# 01_main.net
KiCad netlist of a schematic drawn in Altium Designer
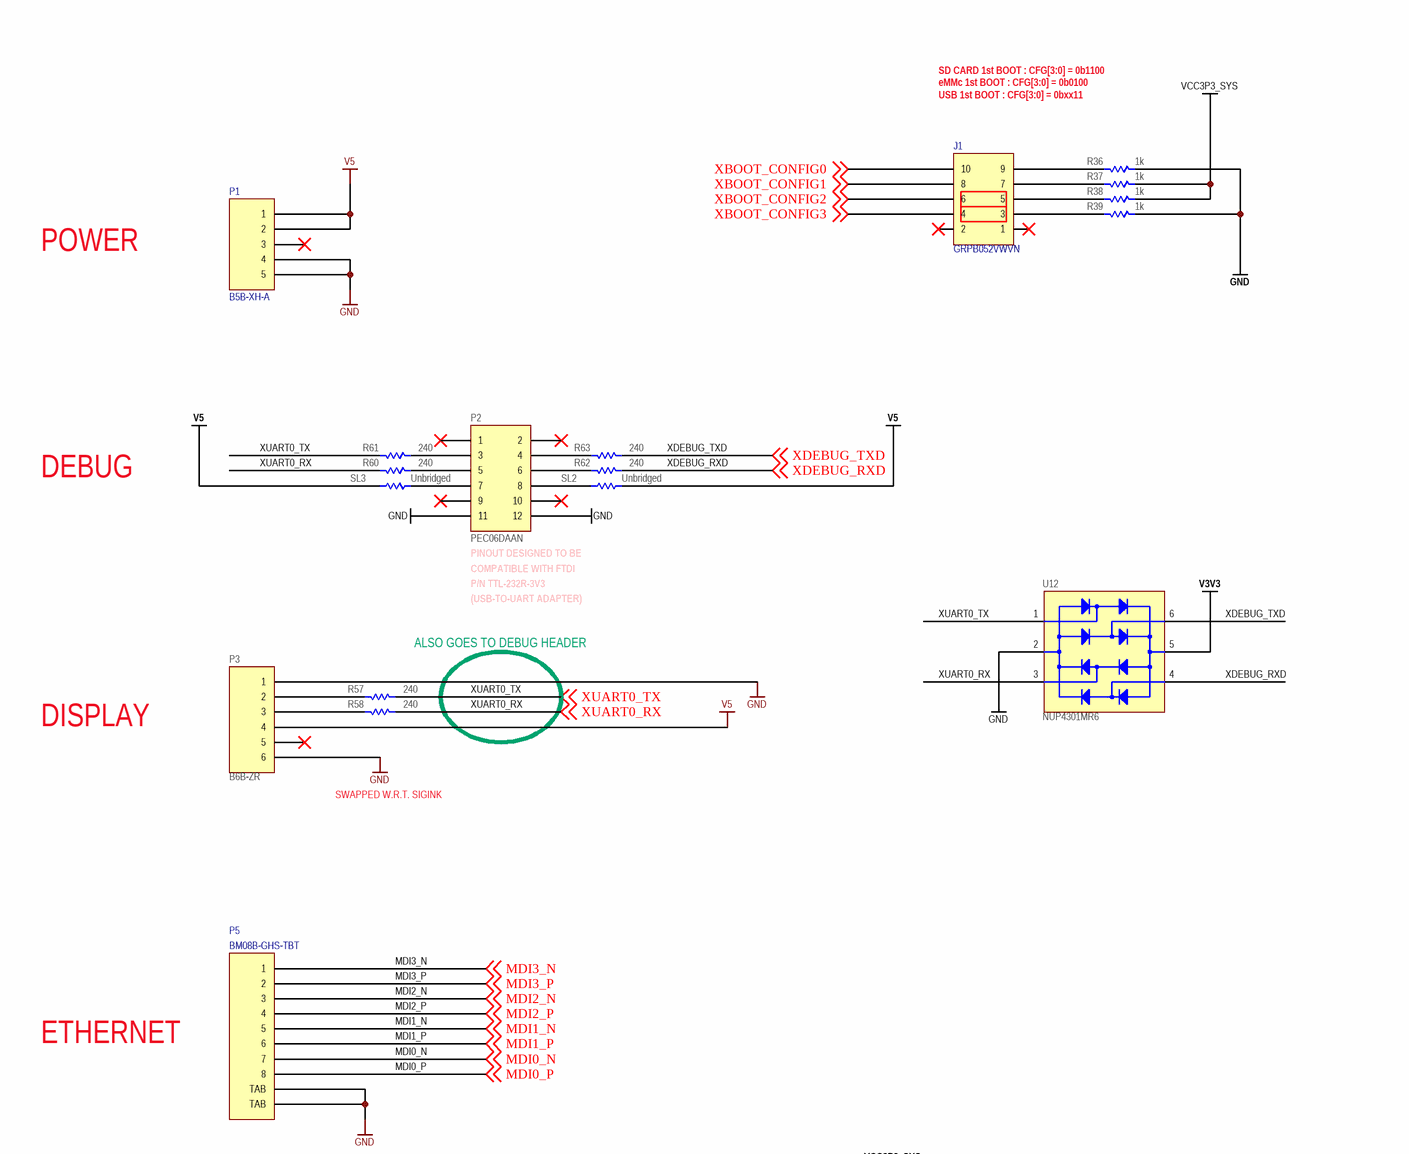
[diagram p0: 01_main.SchDoc, top left]
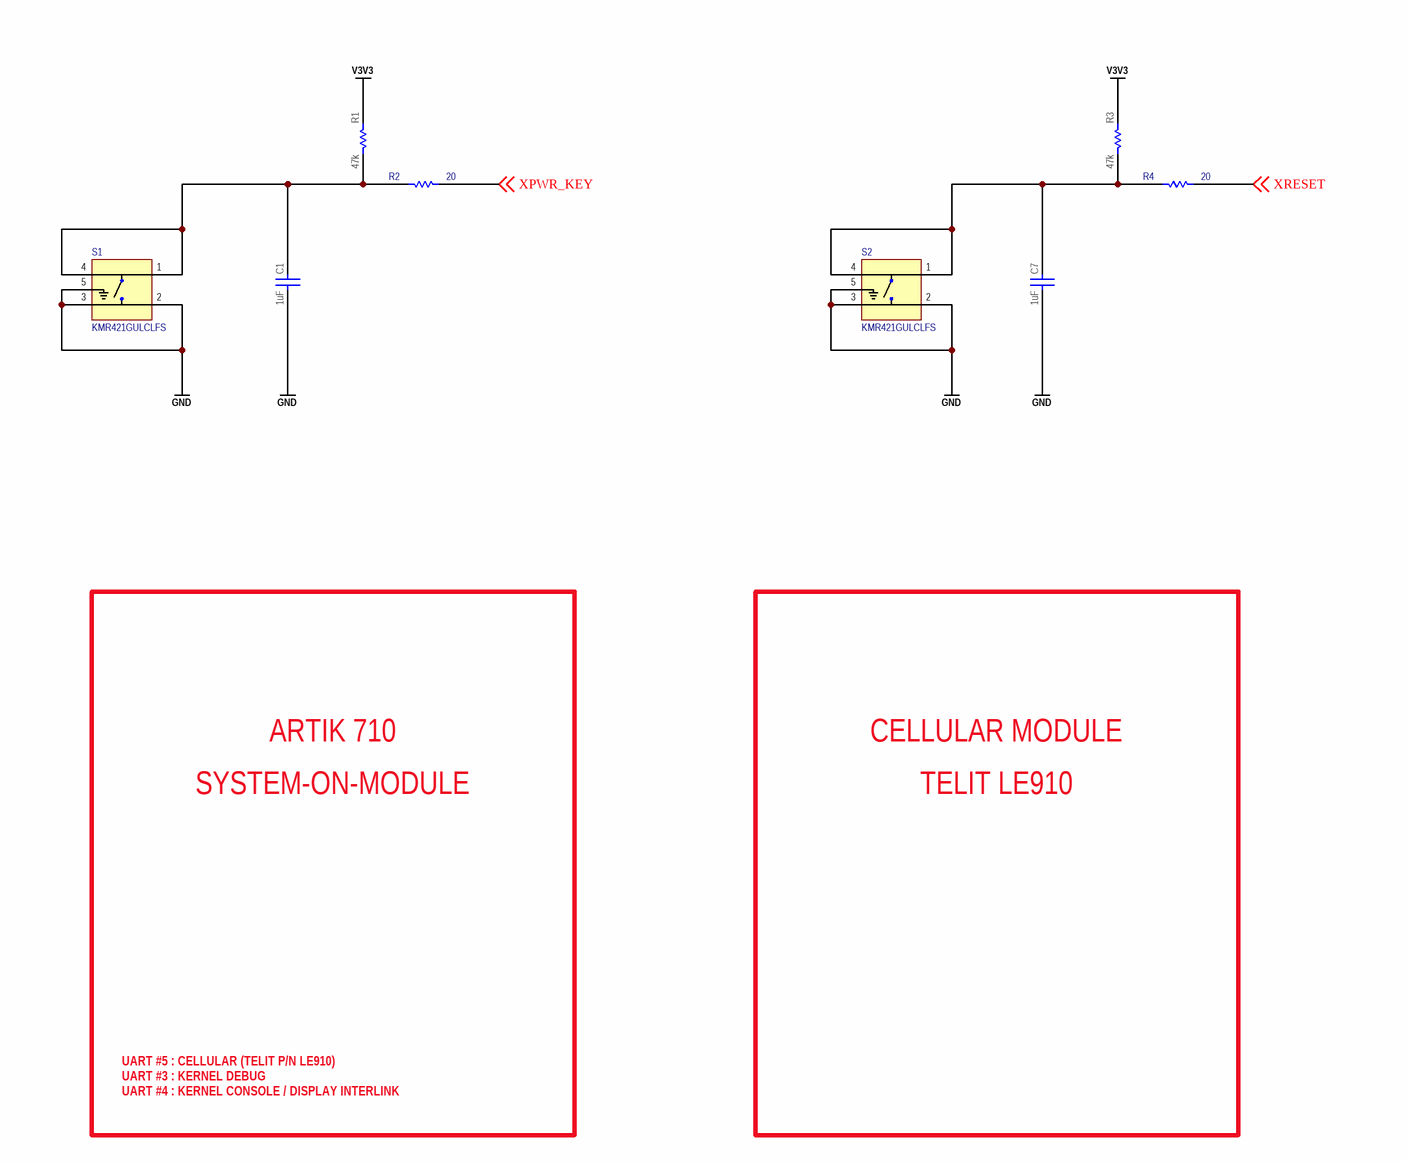
[diagram p1: 01_main.SchDoc, top right]
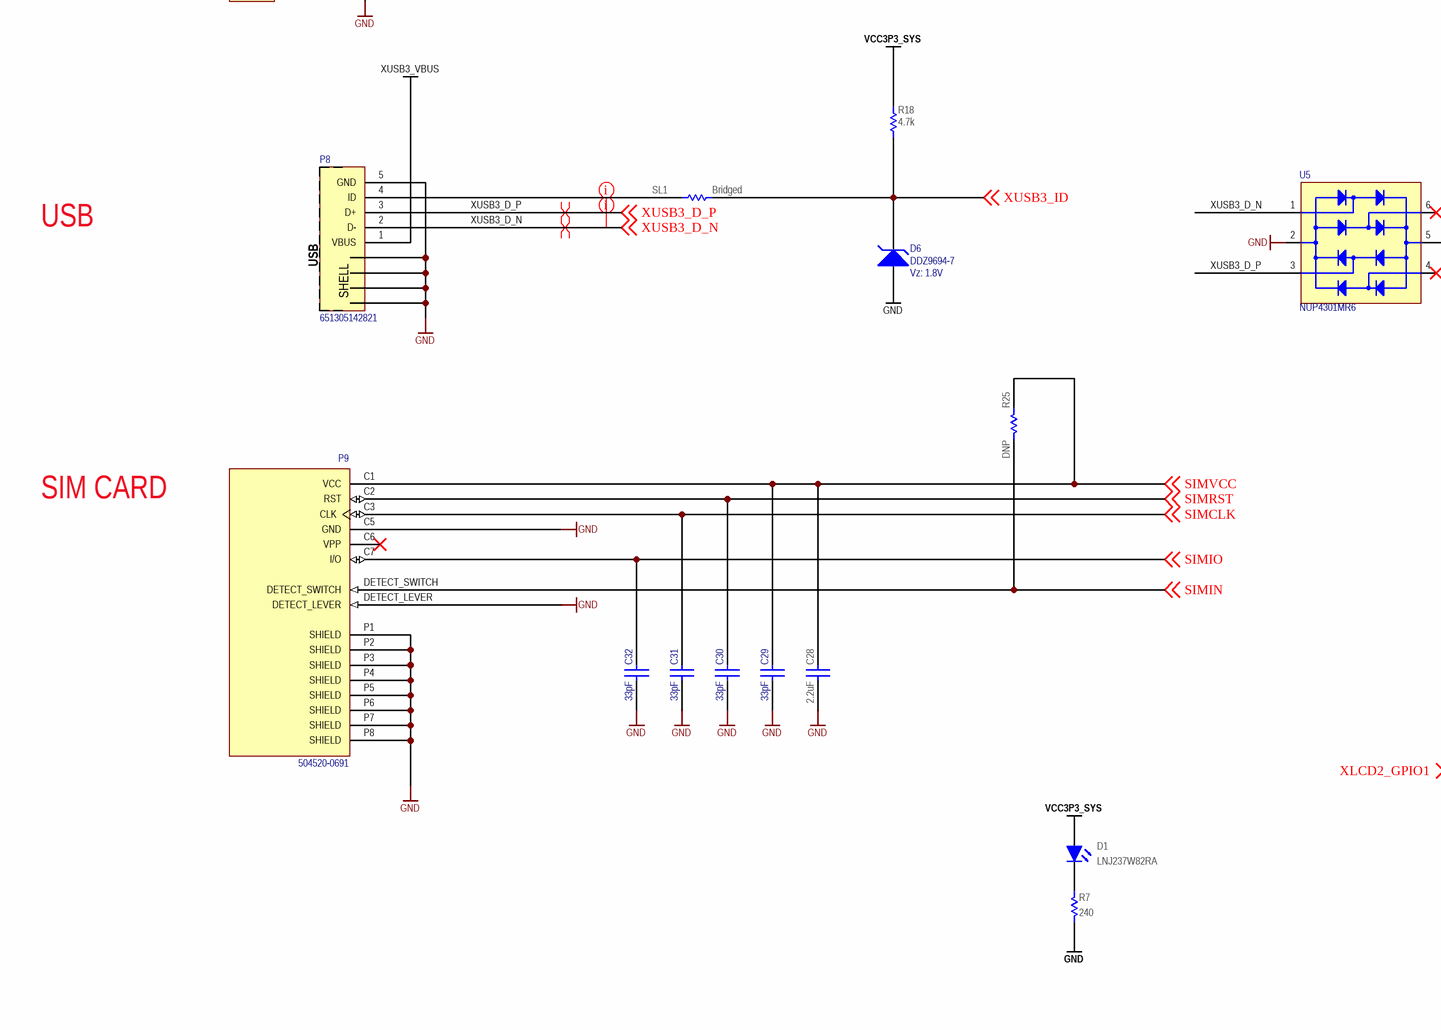
[diagram p2: 01_main.SchDoc, bottom left]
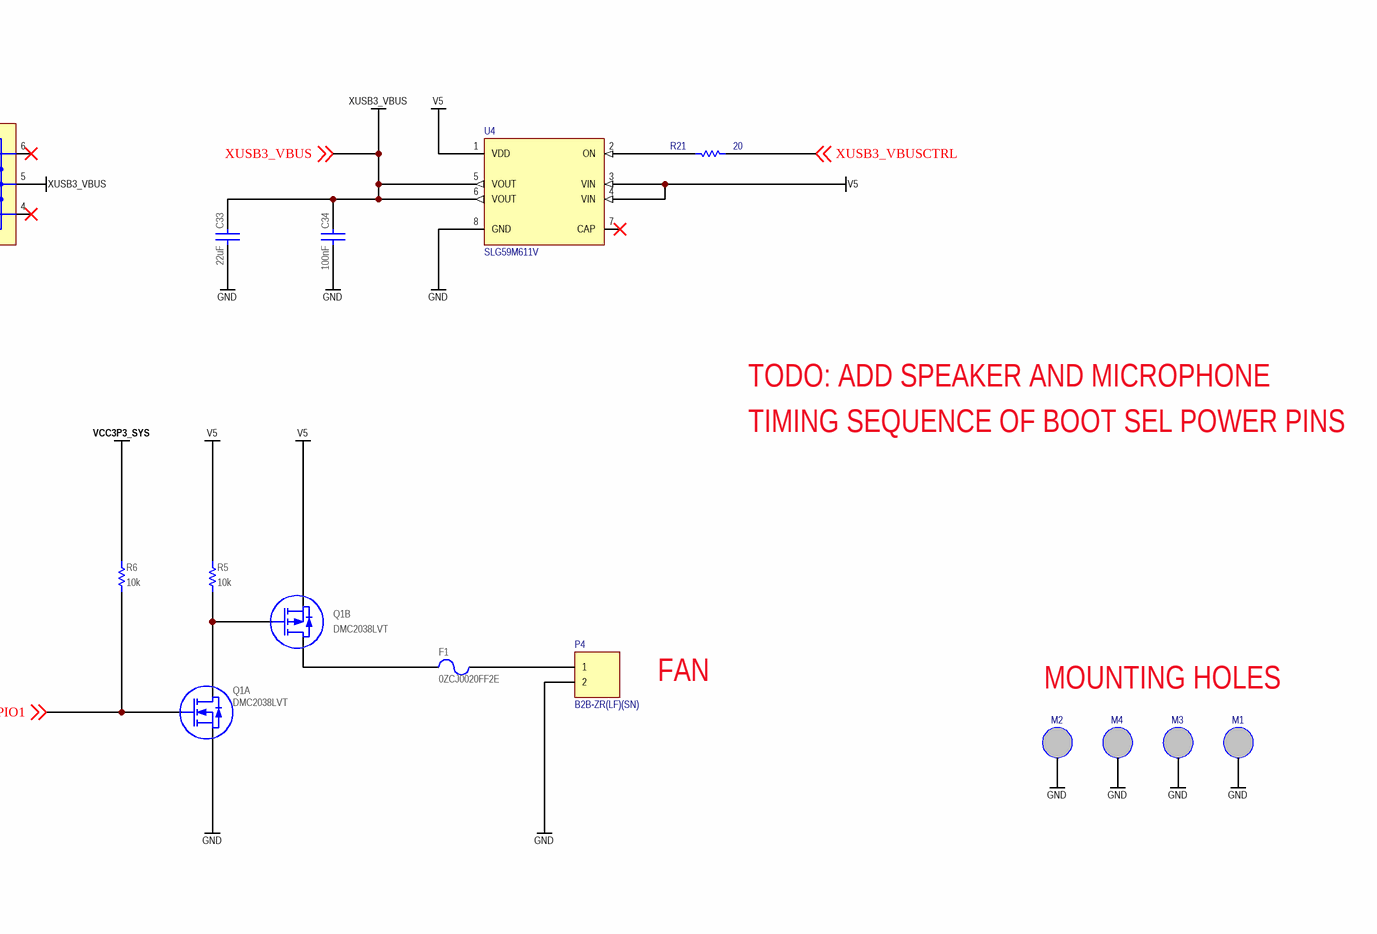
[diagram p3: 01_main.SchDoc, bottom right]

(export (version "E")
  (design (tool "Eeschema 10.0.6"))
  (components
    (comp (ref "C1")
      (value "1uF")
      (footprint "CAPC160X80X90L20N")
      (description "Ceramic Capacitor 1uF ±20% 10V X7R 0603")
      (fields (field (name "MANUFACTURER") "TDK") (field (name "TOLERANCE") "±20%"))
      (libsource (lib "generic") (part "CAP"))
    )
    (comp (ref "C7")
      (value "1uF")
      (footprint "CAPC160X80X90L20N")
      (description "Ceramic Capacitor 1uF ±20% 10V X7R 0603")
      (fields (field (name "MANUFACTURER") "TDK") (field (name "TOLERANCE") "±20%"))
      (libsource (lib "generic") (part "CAP"))
    )
    (comp (ref "C28")
      (value "2.2uF")
      (footprint "CAPC160X80X90L20N")
      (description "Ceramic Capacitor 2.2uF ±20% 10V X7R 0603")
      (fields (field (name "MANUFACTURER") "TDK") (field (name "TOLERANCE") "±20%"))
      (libsource (lib "generic") (part "CAP"))
    )
    (comp (ref "C29")
      (value "33pF")
      (footprint "0402")
      (description "Ceramic Capacitor 33pF ±1% 50V NP0 0402")
      (fields (field (name "VOLTAGE") "50V") (field (name "MANUFACTURER") "Kemet"))
      (libsource (lib "Graviton") (part "CAP 0603"))
    )
    (comp (ref "C30")
      (value "33pF")
      (footprint "0402")
      (description "Ceramic Capacitor 33pF ±1% 50V NP0 0402")
      (fields (field (name "VOLTAGE") "50V") (field (name "MANUFACTURER") "Kemet"))
      (libsource (lib "Graviton") (part "CAP 0603"))
    )
    (comp (ref "C31")
      (value "33pF")
      (footprint "0402")
      (description "Ceramic Capacitor 33pF ±1% 50V NP0 0402")
      (fields (field (name "VOLTAGE") "50V") (field (name "MANUFACTURER") "Kemet"))
      (libsource (lib "Graviton") (part "CAP 0603"))
    )
    (comp (ref "C32")
      (value "33pF")
      (footprint "0402")
      (description "Ceramic Capacitor 33pF ±1% 50V NP0 0402")
      (fields (field (name "VOLTAGE") "50V") (field (name "MANUFACTURER") "Kemet"))
      (libsource (lib "Graviton") (part "CAP 0603"))
    )
    (comp (ref "C33")
      (value "22uF")
      (footprint "CAPC200X125X145L45N")
      (description "Ceramic Capacitor 22uF ±20% 10V X7S 0805")
      (fields (field (name "MANUFACTURER") "TDK") (field (name "TOLERANCE") "±20%"))
      (libsource (lib "generic") (part "CAP"))
    )
    (comp (ref "C34")
      (value "100nF")
      (footprint "CAPC100X50X55L25N")
      (description "Ceramic Capacitor 100nF ±10% 50V X7R 0402")
      (fields (field (name "MANUFACTURER") "Murata") (field (name "TOLERANCE") "±10%"))
      (libsource (lib "generic") (part "CAP"))
    )
    (comp (ref "D1")
      (value "LNJ237W82RA")
      (footprint "0603_LED")
      (description "LED, SMT 0603, Color Red, 5mA, 1.85V")
      (fields (field (name "MANUFACTURER") "Panasonic"))
      (libsource (lib "generic") (part "LED0603RD"))
    )
    (comp (ref "D6")
      (value "DDZ9694-7")
      (footprint "generic:SOD123")
      (description "Zener Diode 1.8V 500mW SOD123")
      (fields (field (name "MANUFACTURER") "Diodes, Inc.") (field (name "VZ") "1.8V"))
      (libsource (lib "diodes_inc") (part "DDZ9694-7"))
    )
    (comp (ref "F1")
      (value "0ZCJ0020FF2E")
      (footprint "generic:1206")
      (description "PTC Resettable Fuse, 0.2A, 30V, SMD 1206")
      (fields (field (name "MANUFACTURER") "Bell Fuse"))
      (libsource (lib "bel-fuse") (part "0ZCJ0020FF2E"))
    )
    (comp (ref "J1")
      (value "GRPB052VWVN")
      (footprint "sullins:GRPB052VWVN")
      (description "Male Header, 0.050\" Pitch, 2x5 Position")
      (fields (field (name "MANUFACTURER") "Sullins"))
      (libsource (lib "sullins") (part "GRPB052VWVN"))
    )
    (comp (ref "M1") (value "MOUNT350") (footprint "mount350") (libsource (lib "Misc") (part "M3_HOLE")))
    (comp (ref "M2") (value "MOUNT350") (footprint "mount350") (libsource (lib "Misc") (part "M3_HOLE")))
    (comp (ref "M3") (value "MOUNT350") (footprint "mount350") (libsource (lib "Misc") (part "M3_HOLE")))
    (comp (ref "M4") (value "MOUNT350") (footprint "mount350") (libsource (lib "Misc") (part "M3_HOLE")))
    (comp (ref "P1")
      (value "B5B-XH-A")
      (footprint "jst:B5B-XH-A")
      (description "2.5mm pitch 5-position")
      (fields (field (name "MANUFACTURER") "JST"))
      (libsource (lib "jst") (part "B5B-XH-A"))
    )
    (comp (ref "P2")
      (value "PEC06DAAN")
      (footprint "HDR2X6")
      (description "Header, 6-Pin, Dual row")
      (fields (field (name "MANUFACTURER") "Sullins"))
      (libsource (lib "Miscellaneous Connectors") (part "Header 6X2H"))
    )
    (comp (ref "P3")
      (value "B6B-ZR")
      (footprint "B6B-ZR")
      (description "Header, 6-Pin, Single row, Vertical")
      (fields (field (name "MANUFACTURER") "JST"))
      (libsource (lib "Sigink") (part "TBD"))
    )
    (comp (ref "P4")
      (value "B2B-ZR(LF)(SN)")
      (footprint "B2B-ZR")
      (description "Header, 2-Pin")
      (fields (field (name "MANUFACTURER") "JST"))
      (libsource (lib "Miscellaneous Connectors") (part "Header 2"))
    )
    (comp (ref "P5")
      (value "BM08B-GHS-TBT")
      (footprint "jst:BM08B-GHS-TBT")
      (description "Top Entry Shrouded Connector; 8-position")
      (fields (field (name "MANUFACTURER") "JST"))
      (libsource (lib "jst") (part "BM08B-GHS-TBT"))
    )
    (comp (ref "P8")
      (value "651305142821")
      (footprint "651305142821")
      (description "Right Angle SMT USB Type-AB Connector Receptacle")
      (fields (field (name "MANUFACTURER") "Wurth Elektronik"))
      (libsource (lib "wurth") (part "651305142821"))
    )
    (comp (ref "P9")
      (value "504520-0691")
      (footprint "504520-0691")
      (description "micro-SIM Card Connector")
      (fields (field (name "MANUFACTURER") "Molex"))
      (libsource (lib "molex") (part "504520-0691"))
    )
    (comp (ref "Q1")
      (value "DMC2038LVT")
      (footprint "generic:TSOP-6")
      (description "Complementary MOSFET Pair")
      (fields (field (name "MANUFACTURER") "Diodes, Inc."))
      (libsource (lib "diodes_inc") (part "DMC2038LVT"))
    )
    (comp (ref "R1")
      (value "47k")
      (footprint "RESC1005X40N")
      (description "Thick Film Resistor 47k ±1% 0.1W 75V 0402")
      (fields (field (name "TOLERANCE") "±1%") (field (name "MANUFACTURER") "Panasonic"))
      (libsource (lib "generic") (part "RES"))
    )
    (comp (ref "R2")
      (value "20")
      (footprint "generic:0402")
      (description "Thick Film Resistor 20 ±1% 0402")
      (fields (field (name "MANUFACTURER") "Panasonic") (field (name "TOLERANCE") "±1%"))
      (libsource (lib "altium-import") (part "root_2_mirrored_RES 0402_"))
    )
    (comp (ref "R3")
      (value "47k")
      (footprint "RESC1005X40N")
      (description "Thick Film Resistor 47k ±1% 0.1W 75V 0402")
      (fields (field (name "TOLERANCE") "±1%") (field (name "MANUFACTURER") "Panasonic"))
      (libsource (lib "generic") (part "RES"))
    )
    (comp (ref "R4")
      (value "20")
      (footprint "generic:0402")
      (description "Thick Film Resistor 20 ±1% 0402")
      (fields (field (name "MANUFACTURER") "Panasonic") (field (name "TOLERANCE") "±1%"))
      (libsource (lib "altium-import") (part "root_2_mirrored_RES 0402_"))
    )
    (comp (ref "R5")
      (value "10k")
      (footprint "RESC1005X40N")
      (description "Thick Film Resistor 10k ±1% 0.1W 0402")
      (fields (field (name "MANUFACTURER") "Panasonic") (field (name "TOLERANCE") "±1%"))
      (libsource (lib "generic") (part "RES"))
    )
    (comp (ref "R6")
      (value "10k")
      (footprint "RESC1005X40N")
      (description "Thick Film Resistor 10k ±1% 0.1W 0402")
      (fields (field (name "MANUFACTURER") "Panasonic") (field (name "TOLERANCE") "±1%"))
      (libsource (lib "generic") (part "RES"))
    )
    (comp (ref "R7")
      (value "240")
      (footprint "RESC1005X40N")
      (description "Thick Film Resistor 240 ±1% 0.1W 75V 0402")
      (fields (field (name "TOLERANCE") "±1%") (field (name "MANUFACTURER") "Panasonic"))
      (libsource (lib "generic") (part "RES"))
    )
    (comp (ref "R18")
      (value "4.7k")
      (footprint "RESC1005X40N")
      (description "Thick Film Resistor 4.7k ±1% 0.1W 75V 0402")
      (fields (field (name "TOLERANCE") "±1%") (field (name "MANUFACTURER") "Panasonic"))
      (libsource (lib "generic") (part "RES"))
    )
    (comp (ref "R21")
      (value "20")
      (footprint "generic:0402")
      (description "Thick Film Resistor 20 ±1% 0402")
      (fields (field (name "MANUFACTURER") "Panasonic") (field (name "TOLERANCE") "±1%"))
      (libsource (lib "altium-import") (part "root_2_mirrored_RES 0402_"))
    )
    (comp (ref "R25")
      (value "ERJ-2RKF4702X")
      (footprint "RESC1005X40N")
      (description "Thick Film Resistor 47k ±1% 0.1W 75V 0402")
      (fields
        (field (name "TOLERANCE") "±1%")
        (field (name "MANUFACTURER") "Panasonic")
        (field (name "DO NOT PLACE") "DNP")
      )
      (libsource (lib "generic") (part "RES"))
    )
    (comp (ref "R36")
      (value "1k")
      (footprint "RESC1005X40N")
      (description "Thick Film Resistor 1k ±1% 0.1W 0402")
      (fields (field (name "TOLERANCE") "±1%") (field (name "MANUFACTURER") "Panasonic"))
      (libsource (lib "generic") (part "RES"))
    )
    (comp (ref "R37")
      (value "1k")
      (footprint "RESC1005X40N")
      (description "Thick Film Resistor 1k ±1% 0.1W 0402")
      (fields (field (name "TOLERANCE") "±1%") (field (name "MANUFACTURER") "Panasonic"))
      (libsource (lib "generic") (part "RES"))
    )
    (comp (ref "R38")
      (value "1k")
      (footprint "RESC1005X40N")
      (description "Thick Film Resistor 1k ±1% 0.1W 0402")
      (fields (field (name "TOLERANCE") "±1%") (field (name "MANUFACTURER") "Panasonic"))
      (libsource (lib "generic") (part "RES"))
    )
    (comp (ref "R39")
      (value "1k")
      (footprint "RESC1005X40N")
      (description "Thick Film Resistor 1k ±1% 0.1W 0402")
      (fields (field (name "TOLERANCE") "±1%") (field (name "MANUFACTURER") "Panasonic"))
      (libsource (lib "generic") (part "RES"))
    )
    (comp (ref "R57")
      (value "240")
      (footprint "RESC1005X40N")
      (description "Thick Film Resistor 240 ±1% 0.1W 75V 0402")
      (fields (field (name "TOLERANCE") "±1%") (field (name "MANUFACTURER") "Panasonic"))
      (libsource (lib "generic") (part "RES"))
    )
    (comp (ref "R58")
      (value "240")
      (footprint "RESC1005X40N")
      (description "Thick Film Resistor 240 ±1% 0.1W 75V 0402")
      (fields (field (name "TOLERANCE") "±1%") (field (name "MANUFACTURER") "Panasonic"))
      (libsource (lib "generic") (part "RES"))
    )
    (comp (ref "R60")
      (value "240")
      (footprint "RESC1005X40N")
      (description "Thick Film Resistor 240 ±1% 0.1W 75V 0402")
      (fields (field (name "TOLERANCE") "±1%") (field (name "MANUFACTURER") "Panasonic"))
      (libsource (lib "generic") (part "RES"))
    )
    (comp (ref "R61")
      (value "240")
      (footprint "RESC1005X40N")
      (description "Thick Film Resistor 240 ±1% 0.1W 75V 0402")
      (fields (field (name "TOLERANCE") "±1%") (field (name "MANUFACTURER") "Panasonic"))
      (libsource (lib "generic") (part "RES"))
    )
    (comp (ref "R62")
      (value "240")
      (footprint "RESC1005X40N")
      (description "Thick Film Resistor 240 ±1% 0.1W 75V 0402")
      (fields (field (name "TOLERANCE") "±1%") (field (name "MANUFACTURER") "Panasonic"))
      (libsource (lib "generic") (part "RES"))
    )
    (comp (ref "R63")
      (value "240")
      (footprint "RESC1005X40N")
      (description "Thick Film Resistor 240 ±1% 0.1W 75V 0402")
      (fields (field (name "TOLERANCE") "±1%") (field (name "MANUFACTURER") "Panasonic"))
      (libsource (lib "generic") (part "RES"))
    )
    (comp (ref "S1")
      (value "KMR421GULCLFS")
      (footprint "SW_KMR421GULCLFS")
      (description "Switch Tactile N.O. SPST Round Button Gull Wing 0.05A 32VDC 1VA 200000Cycles 2N SMD Automotive T/R")
      (fields (field (name "MANUFACTURER") "C&K Components"))
      (libsource (lib "c&k") (part "KMR421GULCLFS"))
    )
    (comp (ref "S2")
      (value "KMR421GULCLFS")
      (footprint "SW_KMR421GULCLFS")
      (description "Switch Tactile N.O. SPST Round Button Gull Wing 0.05A 32VDC 1VA 200000Cycles 2N SMD Automotive T/R")
      (fields (field (name "MANUFACTURER") "C&K Components"))
      (libsource (lib "c&k") (part "KMR421GULCLFS"))
    )
    (comp (ref "SL1")
      (value "Bridged")
      (footprint "SOLDERLINK0603X26N_BRIDGED")
      (description "Solder Link Bridged")
      (fields (field (name "Comment") "SOLDER_LINK_BRIDGED"))
      (libsource (lib "generic") (part "RES"))
    )
    (comp (ref "SL2")
      (value "Unbridged")
      (footprint "SOLDERLINK0603X26N")
      (description "Solder Link Unbridged")
      (fields (field (name "Comment") "SOLDER_LINK"))
      (libsource (lib "generic") (part "RES"))
    )
    (comp (ref "SL3")
      (value "Unbridged")
      (footprint "SOLDERLINK0603X26N")
      (description "Solder Link Unbridged")
      (fields (field (name "Comment") "SOLDER_LINK"))
      (libsource (lib "generic") (part "RES"))
    )
    (comp (ref "U4")
      (value "SLG59M611V")
      (footprint "DFN200X150X80-8N")
      (description "High-Side Load Switch")
      (fields (field (name "MANUFACTURER") "Silego"))
      (libsource (lib "silego") (part "SLG59M611V"))
    )
    (comp (ref "U5")
      (value "NUP4301MR6")
      (footprint "generic:SOT23-6")
      (description "4-Lane TVS Diode Array")
      (fields (field (name "MANUFACTURER") "On Semiconductor"))
      (libsource (lib "on_semi") (part "NUP4301MR6"))
    )
    (comp (ref "U12")
      (value "NUP4301MR6")
      (footprint "generic:SOT23-6")
      (description "4-Lane TVS Diode Array")
      (fields (field (name "MANUFACTURER") "On Semiconductor"))
      (libsource (lib "on_semi") (part "NUP4301MR6"))
    )
  )
  (nets
    (net (code "1") (name "GND") (class "Default")
      (node (ref "C1") (pin "1") (pinfunction "1_1") (pintype "passive"))
      (node (ref "C28") (pin "1") (pinfunction "1_1") (pintype "passive"))
      (node (ref "C29") (pin "2") (pinfunction "2_2") (pintype "passive"))
      (node (ref "C30") (pin "2") (pinfunction "2_2") (pintype "passive"))
      (node (ref "C31") (pin "2") (pinfunction "2_2") (pintype "passive"))
      (node (ref "C32") (pin "2") (pinfunction "2_2") (pintype "passive"))
      (node (ref "C33") (pin "1") (pinfunction "1_1") (pintype "passive"))
      (node (ref "C34") (pin "1") (pinfunction "1_1") (pintype "passive"))
      (node (ref "C7") (pin "1") (pinfunction "1_1") (pintype "passive"))
      (node (ref "D6") (pin "1") (pinfunction "A_1") (pintype "power_in"))
      (node (ref "M1") (pin "1") (pinfunction "GND_1") (pintype "power_in"))
      (node (ref "M2") (pin "1") (pinfunction "GND_1") (pintype "power_in"))
      (node (ref "M3") (pin "1") (pinfunction "GND_1") (pintype "power_in"))
      (node (ref "M4") (pin "1") (pinfunction "GND_1") (pintype "power_in"))
      (node (ref "P1") (pin "4") (pinfunction "4_4") (pintype "passive"))
      (node (ref "P1") (pin "5") (pinfunction "5_5") (pintype "passive"))
      (node (ref "P2") (pin "11") (pinfunction "11_11") (pintype "passive"))
      (node (ref "P2") (pin "12") (pinfunction "12_12") (pintype "passive"))
      (node (ref "P3") (pin "1") (pinfunction "1_1") (pintype "passive"))
      (node (ref "P3") (pin "6") (pinfunction "6_6") (pintype "passive"))
      (node (ref "P4") (pin "2") (pinfunction "2_2") (pintype "passive"))
      (node (ref "P5") (pin "10") (pinfunction "TAB_10") (pintype "passive"))
      (node (ref "P5") (pin "9") (pinfunction "TAB_9") (pintype "passive"))
      (node (ref "P8") (pin "5") (pinfunction "GND_5") (pintype "passive"))
      (node (ref "P8") (pin "SHELL") (pinfunction "SHIELD_SHELL") (pintype "passive"))
      (node (ref "P8") (pin "SHELL1") (pinfunction "SHIELD_SHELL1") (pintype "passive"))
      (node (ref "P8") (pin "SHELL2") (pinfunction "SHIELD_SHELL2") (pintype "passive"))
      (node (ref "P8") (pin "SHELL3") (pinfunction "SHIELD_SHELL3") (pintype "passive"))
      (node (ref "P9") (pin "C5") (pinfunction "GND_C5") (pintype "power_in"))
      (node (ref "P9") (pin "DETECT_LEVER") (pinfunction "DETECT_LEVER_DETECT_LEVER") (pintype "input"))
      (node (ref "P9") (pin "P1") (pinfunction "SHIELD_P1") (pintype "passive"))
      (node (ref "P9") (pin "P2") (pinfunction "SHIELD_P2") (pintype "passive"))
      (node (ref "P9") (pin "P3") (pinfunction "SHIELD_P3") (pintype "passive"))
      (node (ref "P9") (pin "P4") (pinfunction "SHIELD_P4") (pintype "passive"))
      (node (ref "P9") (pin "P5") (pinfunction "SHIELD_P5") (pintype "passive"))
      (node (ref "P9") (pin "P6") (pinfunction "SHIELD_P6") (pintype "passive"))
      (node (ref "P9") (pin "P7") (pinfunction "SHIELD_P7") (pintype "passive"))
      (node (ref "P9") (pin "P8") (pinfunction "SHIELD_P8") (pintype "passive"))
      (node (ref "Q1") (pin "5") (pinfunction "S_5") (pintype "passive"))
      (node (ref "R36") (pin "2") (pinfunction "2_2") (pintype "passive"))
      (node (ref "R39") (pin "2") (pinfunction "2_2") (pintype "passive"))
      (node (ref "R7") (pin "2") (pinfunction "2_2") (pintype "passive"))
      (node (ref "S1") (pin "2") (pinfunction "2_2") (pintype "passive"))
      (node (ref "S1") (pin "3") (pinfunction "3_3") (pintype "passive"))
      (node (ref "S1") (pin "5") (pinfunction "G_5") (pintype "power_in"))
      (node (ref "S2") (pin "2") (pinfunction "2_2") (pintype "passive"))
      (node (ref "S2") (pin "3") (pinfunction "3_3") (pintype "passive"))
      (node (ref "S2") (pin "5") (pinfunction "G_5") (pintype "power_in"))
      (node (ref "U12") (pin "2") (pinfunction "VN_2") (pintype "passive"))
      (node (ref "U4") (pin "8") (pinfunction "GND_8") (pintype "power_in"))
      (node (ref "U5") (pin "2") (pinfunction "VN_2") (pintype "passive"))
    )
    (net (code "2") (name "MDI0_N") (class "Default")
      (node (ref "P5") (pin "7") (pinfunction "7_7") (pintype "passive"))
    )
    (net (code "3") (name "MDI0_P") (class "Default")
      (node (ref "P5") (pin "8") (pinfunction "8_8") (pintype "passive"))
    )
    (net (code "4") (name "MDI1_N") (class "Default")
      (node (ref "P5") (pin "5") (pinfunction "5_5") (pintype "passive"))
    )
    (net (code "5") (name "MDI1_P") (class "Default")
      (node (ref "P5") (pin "6") (pinfunction "6_6") (pintype "passive"))
    )
    (net (code "6") (name "MDI2_N") (class "Default")
      (node (ref "P5") (pin "3") (pinfunction "3_3") (pintype "passive"))
    )
    (net (code "7") (name "MDI2_P") (class "Default")
      (node (ref "P5") (pin "4") (pinfunction "4_4") (pintype "passive"))
    )
    (net (code "8") (name "MDI3_N") (class "Default")
      (node (ref "P5") (pin "1") (pinfunction "1_1") (pintype "passive"))
    )
    (net (code "9") (name "MDI3_P") (class "Default")
      (node (ref "P5") (pin "2") (pinfunction "2_2") (pintype "passive"))
    )
    (net (code "10") (name "Net-(C1-Pad2)") (class "Default")
      (node (ref "C1") (pin "2") (pinfunction "2_2") (pintype "passive"))
      (node (ref "R1") (pin "1") (pinfunction "1_1") (pintype "passive"))
      (node (ref "R2") (pin "1") (pinfunction "1_1") (pintype "passive"))
      (node (ref "S1") (pin "1") (pinfunction "1_1") (pintype "passive"))
      (node (ref "S1") (pin "4") (pinfunction "4_4") (pintype "passive"))
    )
    (net (code "11") (name "Net-(C7-Pad2)") (class "Default")
      (node (ref "C7") (pin "2") (pinfunction "2_2") (pintype "passive"))
      (node (ref "R3") (pin "1") (pinfunction "1_1") (pintype "passive"))
      (node (ref "R4") (pin "1") (pinfunction "1_1") (pintype "passive"))
      (node (ref "S2") (pin "1") (pinfunction "1_1") (pintype "passive"))
      (node (ref "S2") (pin "4") (pinfunction "4_4") (pintype "passive"))
    )
    (net (code "12") (name "Net-(D1-K)") (class "Default")
      (node (ref "D1") (pin "2") (pinfunction "K_2") (pintype "passive"))
      (node (ref "R7") (pin "1") (pinfunction "1_1") (pintype "passive"))
    )
    (net (code "13") (name "Net-(F1-Pad2)") (class "Default")
      (node (ref "F1") (pin "2") (pinfunction "2_2") (pintype "passive"))
      (node (ref "P4") (pin "1") (pinfunction "1_1") (pintype "passive"))
    )
    (net (code "14") (name "Net-(J1-Pad3)") (class "Default")
      (node (ref "J1") (pin "3") (pinfunction "3_3") (pintype "passive"))
      (node (ref "R39") (pin "1") (pinfunction "1_1") (pintype "passive"))
    )
    (net (code "15") (name "Net-(J1-Pad5)") (class "Default")
      (node (ref "J1") (pin "5") (pinfunction "5_5") (pintype "passive"))
      (node (ref "R38") (pin "1") (pinfunction "1_1") (pintype "passive"))
    )
    (net (code "16") (name "Net-(J1-Pad7)") (class "Default")
      (node (ref "J1") (pin "7") (pinfunction "7_7") (pintype "passive"))
      (node (ref "R37") (pin "1") (pinfunction "1_1") (pintype "passive"))
    )
    (net (code "17") (name "Net-(J1-Pad9)") (class "Default")
      (node (ref "J1") (pin "9") (pinfunction "9_9") (pintype "passive"))
      (node (ref "R36") (pin "1") (pinfunction "1_1") (pintype "passive"))
    )
    (net (code "18") (name "Net-(P2-Pad3)") (class "Default")
      (node (ref "P2") (pin "3") (pinfunction "3_3") (pintype "passive"))
      (node (ref "R61") (pin "2") (pinfunction "2_2") (pintype "passive"))
    )
    (net (code "19") (name "Net-(P2-Pad4)") (class "Default")
      (node (ref "P2") (pin "4") (pinfunction "4_4") (pintype "passive"))
      (node (ref "R63") (pin "1") (pinfunction "1_1") (pintype "passive"))
    )
    (net (code "20") (name "Net-(P2-Pad5)") (class "Default")
      (node (ref "P2") (pin "5") (pinfunction "5_5") (pintype "passive"))
      (node (ref "R60") (pin "2") (pinfunction "2_2") (pintype "passive"))
    )
    (net (code "21") (name "Net-(P2-Pad6)") (class "Default")
      (node (ref "P2") (pin "6") (pinfunction "6_6") (pintype "passive"))
      (node (ref "R62") (pin "1") (pinfunction "1_1") (pintype "passive"))
    )
    (net (code "22") (name "Net-(P2-Pad7)") (class "Default")
      (node (ref "P2") (pin "7") (pinfunction "7_7") (pintype "passive"))
      (node (ref "SL3") (pin "2") (pinfunction "2_2") (pintype "passive"))
    )
    (net (code "23") (name "Net-(P2-Pad8)") (class "Default")
      (node (ref "P2") (pin "8") (pinfunction "8_8") (pintype "passive"))
      (node (ref "SL2") (pin "1") (pinfunction "1_1") (pintype "passive"))
    )
    (net (code "24") (name "Net-(P3-Pad2)") (class "Default")
      (node (ref "P3") (pin "2") (pinfunction "2_2") (pintype "passive"))
      (node (ref "R57") (pin "1") (pinfunction "1_1") (pintype "passive"))
    )
    (net (code "25") (name "Net-(P3-Pad3)") (class "Default")
      (node (ref "P3") (pin "3") (pinfunction "3_3") (pintype "passive"))
      (node (ref "R58") (pin "1") (pinfunction "1_1") (pintype "passive"))
    )
    (net (code "26") (name "Net-(P8-ID)") (class "Default")
      (node (ref "P8") (pin "4") (pinfunction "ID_4") (pintype "passive"))
      (node (ref "SL1") (pin "1") (pinfunction "1_1") (pintype "passive"))
    )
    (net (code "27") (name "Net-(Q1A-D)") (class "Default")
      (node (ref "Q1") (pin "3") (pinfunction "G_3") (pintype "passive"))
      (node (ref "Q1") (pin "6") (pinfunction "D_6") (pintype "passive"))
      (node (ref "R5") (pin "1") (pinfunction "1_1") (pintype "passive"))
    )
    (net (code "28") (name "Net-(Q1B-D)") (class "Default")
      (node (ref "F1") (pin "1") (pinfunction "1_1") (pintype "passive"))
      (node (ref "Q1") (pin "4") (pinfunction "D_4") (pintype "passive"))
    )
    (net (code "29") (name "Net-(U4-ON)") (class "Default")
      (node (ref "R21") (pin "1") (pinfunction "1_1") (pintype "passive"))
      (node (ref "U4") (pin "2") (pinfunction "ON_2") (pintype "input"))
    )
    (net (code "30") (name "SIMCLK") (class "Default")
      (node (ref "C31") (pin "1") (pinfunction "1_1") (pintype "passive"))
      (node (ref "P9") (pin "C3") (pinfunction "CLK_C3") (pintype "bidirectional"))
    )
    (net (code "31") (name "SIMIN") (class "Default")
      (node (ref "P9") (pin "DETECT_SWITCH") (pinfunction "DETECT_SWITCH_DETECT_SWITCH") (pintype "input"))
      (node (ref "R25") (pin "1") (pinfunction "1_1") (pintype "passive"))
    )
    (net (code "32") (name "SIMIO") (class "Default")
      (node (ref "C32") (pin "1") (pinfunction "1_1") (pintype "passive"))
      (node (ref "P9") (pin "C7") (pinfunction "I/O_C7") (pintype "bidirectional"))
    )
    (net (code "33") (name "SIMRST") (class "Default")
      (node (ref "C30") (pin "1") (pinfunction "1_1") (pintype "passive"))
      (node (ref "P9") (pin "C2") (pinfunction "RST_C2") (pintype "bidirectional"))
    )
    (net (code "34") (name "SIMVCC") (class "Default")
      (node (ref "C28") (pin "2") (pinfunction "2_2") (pintype "passive"))
      (node (ref "C29") (pin "1") (pinfunction "1_1") (pintype "passive"))
      (node (ref "P9") (pin "C1") (pinfunction "VCC_C1") (pintype "power_in"))
      (node (ref "R25") (pin "2") (pinfunction "2_2") (pintype "passive"))
    )
    (net (code "35") (name "V3V3") (class "Default")
      (node (ref "R1") (pin "2") (pinfunction "2_2") (pintype "passive"))
      (node (ref "R3") (pin "2") (pinfunction "2_2") (pintype "passive"))
      (node (ref "U12") (pin "5") (pinfunction "VP_5") (pintype "passive"))
    )
    (net (code "36") (name "V5") (class "Default")
      (node (ref "P1") (pin "1") (pinfunction "1_1") (pintype "passive"))
      (node (ref "P1") (pin "2") (pinfunction "2_2") (pintype "passive"))
      (node (ref "P3") (pin "4") (pinfunction "4_4") (pintype "passive"))
      (node (ref "Q1") (pin "2") (pinfunction "S_2") (pintype "passive"))
      (node (ref "R5") (pin "2") (pinfunction "2_2") (pintype "passive"))
      (node (ref "SL2") (pin "2") (pinfunction "2_2") (pintype "passive"))
      (node (ref "SL3") (pin "1") (pinfunction "1_1") (pintype "passive"))
      (node (ref "U4") (pin "1") (pinfunction "VDD_1") (pintype "power_in"))
      (node (ref "U4") (pin "3") (pinfunction "VIN_3") (pintype "input"))
      (node (ref "U4") (pin "4") (pinfunction "VIN_4") (pintype "input"))
    )
    (net (code "37") (name "VCC3P3_SYS") (class "Default")
      (node (ref "D1") (pin "1") (pinfunction "A_1") (pintype "passive"))
      (node (ref "R18") (pin "2") (pinfunction "2_2") (pintype "passive"))
      (node (ref "R37") (pin "2") (pinfunction "2_2") (pintype "passive"))
      (node (ref "R38") (pin "2") (pinfunction "2_2") (pintype "passive"))
      (node (ref "R6") (pin "2") (pinfunction "2_2") (pintype "passive"))
    )
    (net (code "38") (name "XBOOT_CONFIG0") (class "Default")
      (node (ref "J1") (pin "10") (pinfunction "10_10") (pintype "passive"))
    )
    (net (code "39") (name "XBOOT_CONFIG1") (class "Default")
      (node (ref "J1") (pin "8") (pinfunction "8_8") (pintype "passive"))
    )
    (net (code "40") (name "XBOOT_CONFIG2") (class "Default")
      (node (ref "J1") (pin "6") (pinfunction "6_6") (pintype "passive"))
    )
    (net (code "41") (name "XBOOT_CONFIG3") (class "Default")
      (node (ref "J1") (pin "4") (pinfunction "4_4") (pintype "passive"))
    )
    (net (code "42") (name "XDEBUG_RXD") (class "Default")
      (node (ref "R62") (pin "2") (pinfunction "2_2") (pintype "passive"))
      (node (ref "U12") (pin "4") (pinfunction "C_4") (pintype "passive"))
    )
    (net (code "43") (name "XDEBUG_TXD") (class "Default")
      (node (ref "R63") (pin "2") (pinfunction "2_2") (pintype "passive"))
      (node (ref "U12") (pin "6") (pinfunction "D_6") (pintype "passive"))
    )
    (net (code "44") (name "XLCD2_GPIO1") (class "Default")
      (node (ref "Q1") (pin "1") (pinfunction "G_1") (pintype "passive"))
      (node (ref "R6") (pin "1") (pinfunction "1_1") (pintype "passive"))
    )
    (net (code "45") (name "XPWR_KEY") (class "Default")
      (node (ref "R2") (pin "2") (pinfunction "2_2") (pintype "passive"))
    )
    (net (code "46") (name "XRESET") (class "Default")
      (node (ref "R4") (pin "2") (pinfunction "2_2") (pintype "passive"))
    )
    (net (code "47") (name "XUART0_RX") (class "Default")
      (node (ref "R58") (pin "2") (pinfunction "2_2") (pintype "passive"))
      (node (ref "R60") (pin "1") (pinfunction "1_1") (pintype "passive"))
      (node (ref "U12") (pin "3") (pinfunction "B_3") (pintype "passive"))
    )
    (net (code "48") (name "XUART0_TX") (class "Default")
      (node (ref "R57") (pin "2") (pinfunction "2_2") (pintype "passive"))
      (node (ref "R61") (pin "1") (pinfunction "1_1") (pintype "passive"))
      (node (ref "U12") (pin "1") (pinfunction "A_1") (pintype "passive"))
    )
    (net (code "49") (name "XUSB3_D_N") (class "Default")
      (node (ref "P8") (pin "2") (pinfunction "D-_2") (pintype "passive"))
      (node (ref "U5") (pin "1") (pinfunction "A_1") (pintype "passive"))
    )
    (net (code "50") (name "XUSB3_D_P") (class "Default")
      (node (ref "P8") (pin "3") (pinfunction "D+_3") (pintype "passive"))
      (node (ref "U5") (pin "3") (pinfunction "B_3") (pintype "passive"))
    )
    (net (code "51") (name "XUSB3_ID") (class "Default")
      (node (ref "D6") (pin "2") (pinfunction "C_2") (pintype "passive"))
      (node (ref "R18") (pin "1") (pinfunction "1_1") (pintype "passive"))
      (node (ref "SL1") (pin "2") (pinfunction "2_2") (pintype "passive"))
    )
    (net (code "52") (name "XUSB3_VBUS") (class "Default")
      (node (ref "C33") (pin "2") (pinfunction "2_2") (pintype "passive"))
      (node (ref "C34") (pin "2") (pinfunction "2_2") (pintype "passive"))
      (node (ref "P8") (pin "1") (pinfunction "VBUS_1") (pintype "passive"))
      (node (ref "U4") (pin "5") (pinfunction "VOUT_5") (pintype "output"))
      (node (ref "U4") (pin "6") (pinfunction "VOUT_6") (pintype "output"))
      (node (ref "U5") (pin "5") (pinfunction "VP_5") (pintype "passive"))
    )
    (net (code "53") (name "XUSB3_VBUSCTRL") (class "Default")
      (node (ref "R21") (pin "2") (pinfunction "2_2") (pintype "passive"))
    )
    (net (code "54") (name "unconnected-(J1-Pad1)") (class "Default")
      (node (ref "J1") (pin "1") (pinfunction "1_1") (pintype "passive+no_connect"))
    )
    (net (code "55") (name "unconnected-(J1-Pad2)") (class "Default")
      (node (ref "J1") (pin "2") (pinfunction "2_2") (pintype "passive+no_connect"))
    )
    (net (code "56") (name "unconnected-(P1-Pad3)") (class "Default")
      (node (ref "P1") (pin "3") (pinfunction "3_3") (pintype "passive+no_connect"))
    )
    (net (code "57") (name "unconnected-(P2-Pad1)") (class "Default")
      (node (ref "P2") (pin "1") (pinfunction "1_1") (pintype "passive+no_connect"))
    )
    (net (code "58") (name "unconnected-(P2-Pad2)") (class "Default")
      (node (ref "P2") (pin "2") (pinfunction "2_2") (pintype "passive+no_connect"))
    )
    (net (code "59") (name "unconnected-(P2-Pad9)") (class "Default")
      (node (ref "P2") (pin "9") (pinfunction "9_9") (pintype "passive+no_connect"))
    )
    (net (code "60") (name "unconnected-(P2-Pad10)") (class "Default")
      (node (ref "P2") (pin "10") (pinfunction "10_10") (pintype "passive+no_connect"))
    )
    (net (code "61") (name "unconnected-(P3-Pad5)") (class "Default")
      (node (ref "P3") (pin "5") (pinfunction "5_5") (pintype "passive+no_connect"))
    )
    (net (code "62") (name "unconnected-(P9-VPP-PadC6)") (class "Default")
      (node (ref "P9") (pin "C6") (pinfunction "VPP_C6") (pintype "power_in+no_connect"))
    )
    (net (code "63") (name "unconnected-(U4-CAP-Pad7)") (class "Default")
      (node (ref "U4") (pin "7") (pinfunction "CAP_7") (pintype "passive+no_connect"))
    )
    (net (code "64") (name "unconnected-(U5-C-Pad4)") (class "Default")
      (node (ref "U5") (pin "4") (pinfunction "C_4") (pintype "passive+no_connect"))
    )
    (net (code "65") (name "unconnected-(U5-D-Pad6)") (class "Default")
      (node (ref "U5") (pin "6") (pinfunction "D_6") (pintype "passive+no_connect"))
    )
  )
)
